# attiny85.net
KiCad netlist of a schematic drawn in EAGLE
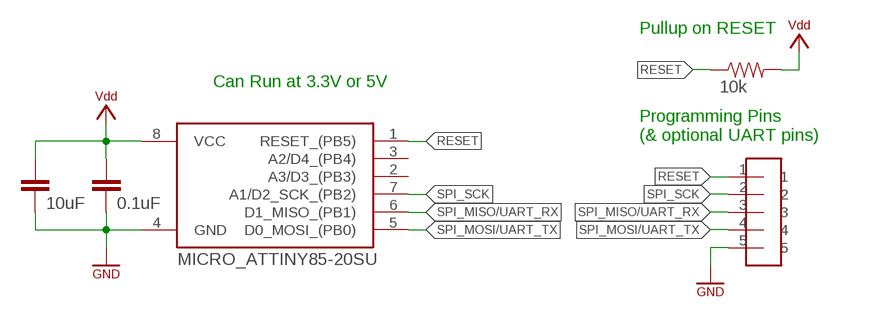
[diagram p0: schematic, sheet 1]

(export (version "E")
  (design (tool "Eeschema 10.0.6"))
  (components
    (comp (ref "C1")
      (value "0.1uF")
      (footprint "eagle-import:0805")
      (libsource (lib "eagle-import") (part "COMPONENT_CAP-0805"))
    )
    (comp (ref "C2")
      (value "10uF")
      (footprint "eagle-import:0805")
      (libsource (lib "eagle-import") (part "COMPONENT_CAP-0805"))
    )
    (comp (ref "R1")
      (value "10k")
      (footprint "eagle-import:0805")
      (libsource (lib "eagle-import") (part "COMPONENT_RESISTOR-0805"))
    )
    (comp (ref "U$1")
      (value "MICRO_ATTINY85-20SU")
      (footprint "eagle-import:SOIC8")
      (libsource (lib "eagle-import") (part "MICRO_ATTINY85-20SU"))
    )
    (comp (ref "U$2")
      (value "HEADER-5-TESTPOINT")
      (footprint "eagle-import:TESTPOINT-5")
      (libsource (lib "eagle-import") (part "HEADER-5-TESTPOINT"))
    )
  )
  (nets
    (net (code "1") (name "RESET") (class "Default")
      (node (ref "R1") (pin "1") (pinfunction "1_1") (pintype "passive"))
      (node (ref "U$1") (pin "1") (pinfunction "RESET_(PB5)_1") (pintype "bidirectional"))
      (node (ref "U$2") (pin "1") (pinfunction "1_1") (pintype "bidirectional"))
    )
    (net (code "2") (name "SPI_MISO{slash}UART_RX") (class "Default")
      (node (ref "U$1") (pin "6") (pinfunction "D1_MISO_(PB1)_6") (pintype "bidirectional"))
      (node (ref "U$2") (pin "3") (pinfunction "3_3") (pintype "bidirectional"))
    )
    (net (code "3") (name "SPI_MOSI{slash}UART_TX") (class "Default")
      (node (ref "U$1") (pin "5") (pinfunction "D0_MOSI_(PB0)_5") (pintype "bidirectional"))
      (node (ref "U$2") (pin "4") (pinfunction "4_4") (pintype "bidirectional"))
    )
    (net (code "4") (name "SPI_SCK") (class "Default")
      (node (ref "U$1") (pin "7") (pinfunction "A1/D2_SCK_(PB2)_7") (pintype "bidirectional"))
      (node (ref "U$2") (pin "2") (pinfunction "2_2") (pintype "bidirectional"))
    )
    (net (code "5") (name "SYMBOL_GND") (class "Default")
      (node (ref "C1") (pin "2") (pinfunction "2_2") (pintype "passive"))
      (node (ref "C2") (pin "2") (pinfunction "2_2") (pintype "passive"))
      (node (ref "U$1") (pin "4") (pinfunction "GND_4") (pintype "power_in"))
      (node (ref "U$2") (pin "5") (pinfunction "5_5") (pintype "bidirectional"))
    )
    (net (code "6") (name "SYMBOL_VDD") (class "Default")
      (node (ref "C1") (pin "1") (pinfunction "1_1") (pintype "passive"))
      (node (ref "C2") (pin "1") (pinfunction "1_1") (pintype "passive"))
      (node (ref "R1") (pin "2") (pinfunction "2_2") (pintype "passive"))
      (node (ref "U$1") (pin "8") (pinfunction "VCC_8") (pintype "power_in"))
    )
    (net (code "7") (name "unconnected-(U$1-A2{slash}D4_(PB4)-Pad3)") (class "Default")
      (node (ref "U$1") (pin "3") (pinfunction "A2/D4_(PB4)_3") (pintype "bidirectional"))
    )
    (net (code "8") (name "unconnected-(U$1-A3{slash}D3_(PB3)-Pad2)") (class "Default")
      (node (ref "U$1") (pin "2") (pinfunction "A3/D3_(PB3)_2") (pintype "bidirectional"))
    )
  )
)
